# My-Stomp_1_1.net
KiCad netlist of a schematic drawn in EAGLE
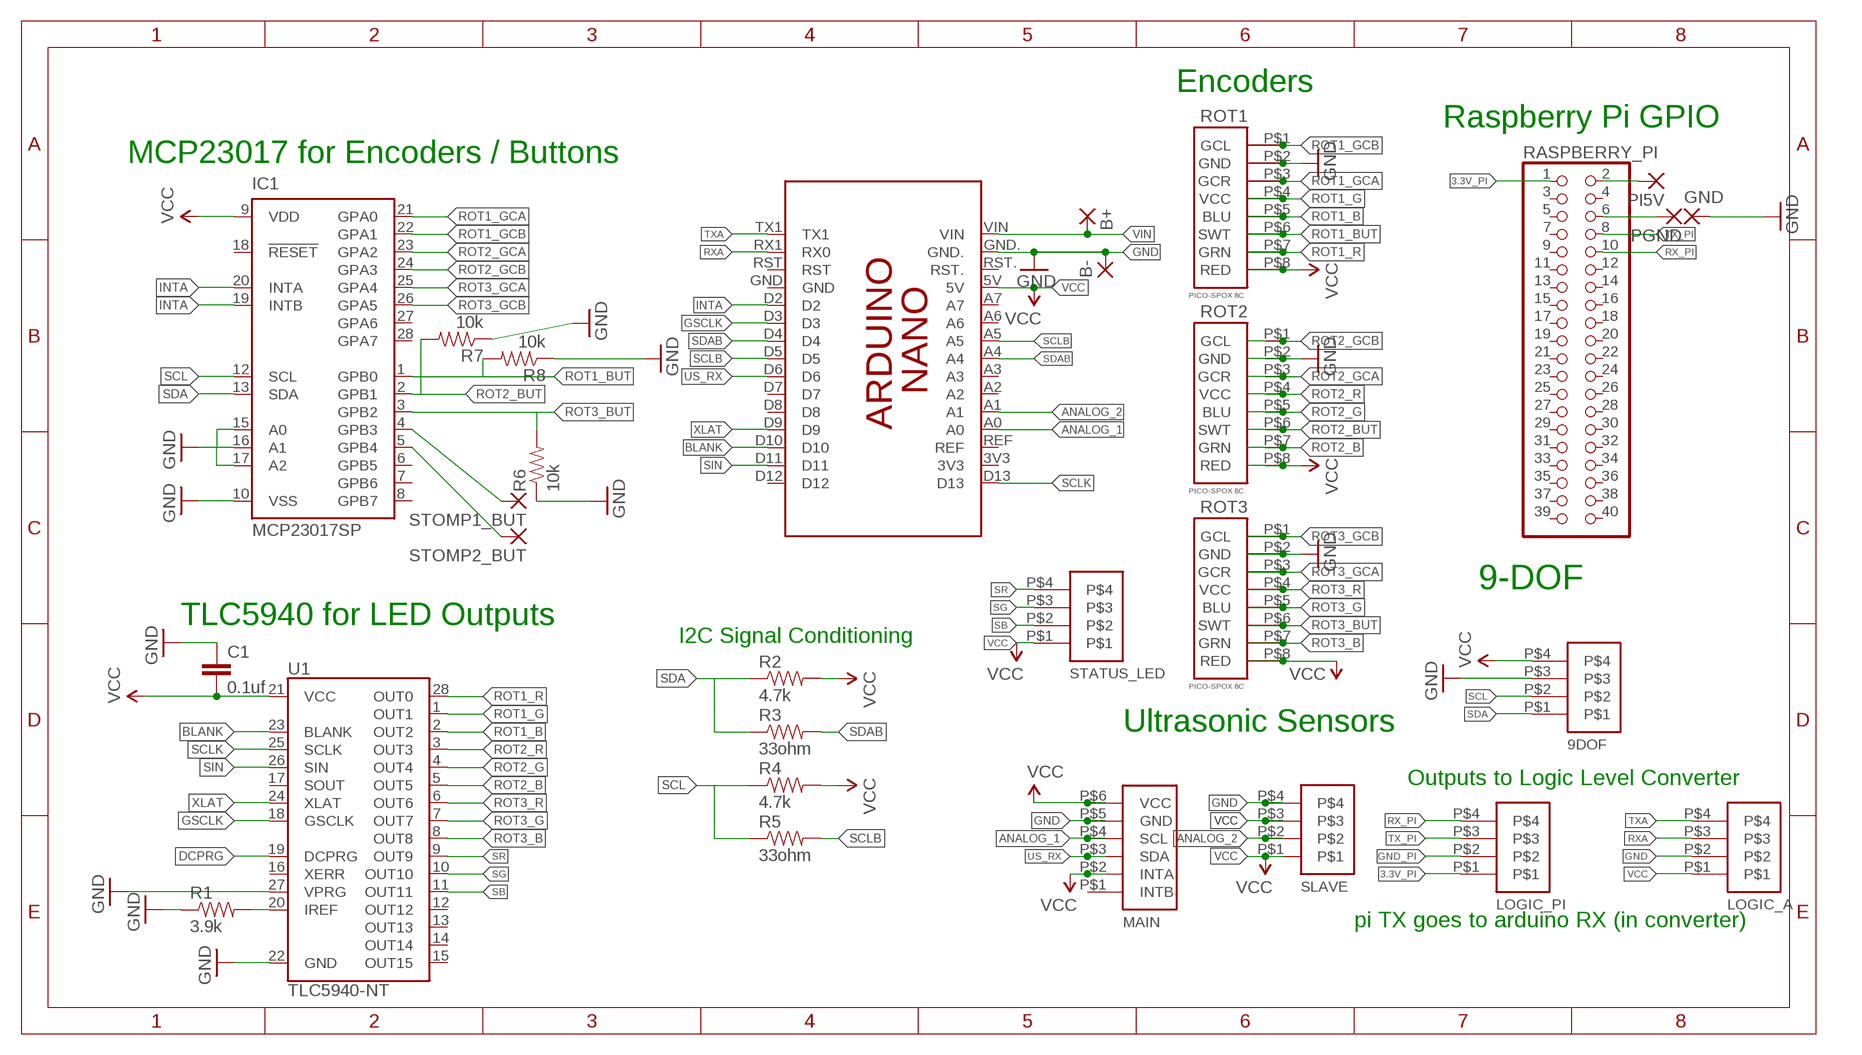
[diagram p0: schematic, sheet 1]

(export (version "E")
  (design (tool "Eeschema 10.0.6"))
  (components
    (comp (ref "9DOF")
      (value "PICO_SPOX_4C")
      (footprint "eagle-import:PICO_SPOX_4C")
      (libsource (lib "eagle-import") (part "PICO_SPOX_4C"))
    )
    (comp (ref "B+")
      (value "2,15/1,0")
      (footprint "eagle-import:2,15_1,0")
      (libsource (lib "eagle-import") (part "2,15/1,0"))
    )
    (comp (ref "B-")
      (value "2,15/1,0")
      (footprint "eagle-import:2,15_1,0")
      (libsource (lib "eagle-import") (part "2,15/1,0"))
    )
    (comp (ref "C1")
      (value "0.1uf")
      (footprint "eagle-import:CAP-PTH-5MM")
      (libsource (lib "eagle-import") (part "CAPPTH1"))
    )
    (comp (ref "GND")
      (value "2,15/1,0")
      (footprint "eagle-import:2,15_1,0")
      (libsource (lib "eagle-import") (part "2,15/1,0"))
    )
    (comp (ref "IC1")
      (value "MCP23017SP")
      (footprint "eagle-import:DIL28-3")
      (libsource (lib "eagle-import") (part "MCP23017SP"))
    )
    (comp (ref "LOGIC_A")
      (value "PICO_SPOX_4C")
      (footprint "eagle-import:PICO_SPOX_4C")
      (libsource (lib "eagle-import") (part "PICO_SPOX_4C"))
    )
    (comp (ref "LOGIC_PI")
      (value "PICO_SPOX_4C")
      (footprint "eagle-import:PICO_SPOX_4C")
      (libsource (lib "eagle-import") (part "PICO_SPOX_4C"))
    )
    (comp (ref "MAIN")
      (value "PICO_SPOX_6C")
      (footprint "eagle-import:PICO_SPOX_6C")
      (libsource (lib "eagle-import") (part "PICO_SPOX_6C"))
    )
    (comp (ref "PCB2")
      (value "ARDUINO_NANO")
      (footprint "eagle-import:ARDUINO_NANO")
      (libsource (lib "eagle-import") (part "ARDUINO_NANO"))
    )
    (comp (ref "PGND")
      (value "2,15/1,0")
      (footprint "eagle-import:2,15_1,0")
      (libsource (lib "eagle-import") (part "2,15/1,0"))
    )
    (comp (ref "PI5V")
      (value "2,15/1,0")
      (footprint "eagle-import:2,15_1,0")
      (libsource (lib "eagle-import") (part "2,15/1,0"))
    )
    (comp (ref "R1")
      (value "3.9k")
      (footprint "eagle-import:AXIAL-0.3")
      (libsource (lib "eagle-import") (part "RESISTORPTH1"))
    )
    (comp (ref "R2")
      (value "4.7k")
      (footprint "eagle-import:AXIAL-0.3")
      (libsource (lib "eagle-import") (part "RESISTORPTH1"))
    )
    (comp (ref "R3")
      (value "33ohm")
      (footprint "eagle-import:AXIAL-0.3")
      (libsource (lib "eagle-import") (part "RESISTORPTH1"))
    )
    (comp (ref "R4")
      (value "4.7k")
      (footprint "eagle-import:AXIAL-0.3")
      (libsource (lib "eagle-import") (part "RESISTORPTH1"))
    )
    (comp (ref "R5")
      (value "33ohm")
      (footprint "eagle-import:AXIAL-0.3")
      (libsource (lib "eagle-import") (part "RESISTORPTH1"))
    )
    (comp (ref "R6")
      (value "10k")
      (footprint "eagle-import:AXIAL-0.3")
      (libsource (lib "eagle-import") (part "RESISTORPTH1"))
    )
    (comp (ref "R7")
      (value "10k")
      (footprint "eagle-import:AXIAL-0.3")
      (libsource (lib "eagle-import") (part "RESISTORPTH1"))
    )
    (comp (ref "R8")
      (value "10k")
      (footprint "eagle-import:AXIAL-0.3")
      (libsource (lib "eagle-import") (part "RESISTORPTH1"))
    )
    (comp (ref "RASPBERRY_PI")
      (value "PINHD-2X20")
      (footprint "eagle-import:2X20")
      (libsource (lib "eagle-import") (part "PINHD-2X20"))
    )
    (comp (ref "ROT1")
      (value "PICO_SPOX_8C")
      (footprint "eagle-import:PICO_SPOC_8C")
      (libsource (lib "eagle-import") (part "PICO_SPOX_8C"))
    )
    (comp (ref "ROT2")
      (value "PICO_SPOX_8C")
      (footprint "eagle-import:PICO_SPOC_8C")
      (libsource (lib "eagle-import") (part "PICO_SPOX_8C"))
    )
    (comp (ref "ROT3")
      (value "PICO_SPOX_8C")
      (footprint "eagle-import:PICO_SPOC_8C")
      (libsource (lib "eagle-import") (part "PICO_SPOX_8C"))
    )
    (comp (ref "SLAVE")
      (value "PICO_SPOX_4C")
      (footprint "eagle-import:PICO_SPOX_4C")
      (libsource (lib "eagle-import") (part "PICO_SPOX_4C"))
    )
    (comp (ref "STATUS_LED")
      (value "PICO_SPOX_4C")
      (footprint "eagle-import:PICO_SPOX_4C")
      (libsource (lib "eagle-import") (part "PICO_SPOX_4C"))
    )
    (comp (ref "STOMP1_BUT")
      (value "2,15/1,0")
      (footprint "eagle-import:2,15_1,0")
      (libsource (lib "eagle-import") (part "2,15/1,0"))
    )
    (comp (ref "STOMP2_BUT")
      (value "2,15/1,0")
      (footprint "eagle-import:2,15_1,0")
      (libsource (lib "eagle-import") (part "2,15/1,0"))
    )
    (comp (ref "U1")
      (value "TLC5940-NT")
      (footprint "eagle-import:DIL28-3")
      (libsource (lib "eagle-import") (part "TLC5940-NT"))
    )
  )
  (nets
    (net (code "1") (name "3.3V_PI") (class "Default")
      (node (ref "LOGIC_PI") (pin "P$1") (pinfunction "P$1_P$1") (pintype "bidirectional"))
      (node (ref "RASPBERRY_PI") (pin "1") (pinfunction "1_1") (pintype "passive"))
    )
    (net (code "2") (name "ANALOG_1") (class "Default")
      (node (ref "MAIN") (pin "P$4") (pinfunction "SCL_P$4") (pintype "bidirectional"))
      (node (ref "PCB2") (pin "A0") (pinfunction "A0_A0") (pintype "bidirectional"))
    )
    (net (code "3") (name "ANALOG_2") (class "Default")
      (node (ref "PCB2") (pin "A1") (pinfunction "A1_A1") (pintype "bidirectional"))
      (node (ref "SLAVE") (pin "P$2") (pinfunction "P$2_P$2") (pintype "bidirectional"))
    )
    (net (code "4") (name "BLANK") (class "Default")
      (node (ref "PCB2") (pin "D10") (pinfunction "D10_D10") (pintype "bidirectional"))
      (node (ref "U1") (pin "23") (pinfunction "BLANK_23") (pintype "bidirectional"))
    )
    (net (code "5") (name "DCPRG") (class "Default")
      (node (ref "U1") (pin "19") (pinfunction "DCPRG_19") (pintype "bidirectional"))
    )
    (net (code "6") (name "GND") (class "Default")
      (node (ref "9DOF") (pin "P$3") (pinfunction "P$3_P$3") (pintype "bidirectional"))
      (node (ref "B-") (pin "1") (pinfunction "P_1") (pintype "passive"))
      (node (ref "C1") (pin "1") (pinfunction "1_1") (pintype "passive"))
      (node (ref "GND") (pin "1") (pinfunction "P_1") (pintype "passive"))
      (node (ref "IC1") (pin "10") (pinfunction "VSS_10") (pintype "power_in"))
      (node (ref "IC1") (pin "15") (pinfunction "A0_15") (pintype "input"))
      (node (ref "IC1") (pin "16") (pinfunction "A1_16") (pintype "input"))
      (node (ref "IC1") (pin "17") (pinfunction "A2_17") (pintype "input"))
      (node (ref "LOGIC_A") (pin "P$2") (pinfunction "P$2_P$2") (pintype "bidirectional"))
      (node (ref "MAIN") (pin "P$5") (pinfunction "GND_P$5") (pintype "bidirectional"))
      (node (ref "PCB2") (pin "GND.") (pinfunction "GND._GND.") (pintype "bidirectional"))
      (node (ref "R1") (pin "P$1") (pinfunction "1_P$1") (pintype "passive"))
      (node (ref "R6") (pin "P$1") (pinfunction "1_P$1") (pintype "passive"))
      (node (ref "R7") (pin "P$1") (pinfunction "1_P$1") (pintype "passive"))
      (node (ref "R8") (pin "P$1") (pinfunction "1_P$1") (pintype "passive"))
      (node (ref "ROT1") (pin "P$2") (pinfunction "GND_P$2") (pintype "bidirectional"))
      (node (ref "ROT2") (pin "P$2") (pinfunction "GND_P$2") (pintype "bidirectional"))
      (node (ref "ROT3") (pin "P$2") (pinfunction "GND_P$2") (pintype "bidirectional"))
      (node (ref "SLAVE") (pin "P$4") (pinfunction "P$4_P$4") (pintype "bidirectional"))
      (node (ref "U1") (pin "22") (pinfunction "GND_22") (pintype "bidirectional"))
      (node (ref "U1") (pin "27") (pinfunction "VPRG_27") (pintype "bidirectional"))
    )
    (net (code "7") (name "GND_PI") (class "Default")
      (node (ref "LOGIC_PI") (pin "P$2") (pinfunction "P$2_P$2") (pintype "bidirectional"))
      (node (ref "PGND") (pin "1") (pinfunction "P_1") (pintype "passive"))
      (node (ref "RASPBERRY_PI") (pin "6") (pinfunction "6_6") (pintype "passive"))
    )
    (net (code "8") (name "GSCLK") (class "Default")
      (node (ref "PCB2") (pin "D3") (pinfunction "D3_D3") (pintype "bidirectional"))
      (node (ref "U1") (pin "18") (pinfunction "GSCLK_18") (pintype "bidirectional"))
    )
    (net (code "9") (name "INTA") (class "Default")
      (node (ref "IC1") (pin "19") (pinfunction "INTB_19") (pintype "output"))
      (node (ref "IC1") (pin "20") (pinfunction "INTA_20") (pintype "output"))
      (node (ref "PCB2") (pin "D2") (pinfunction "D2_D2") (pintype "bidirectional"))
    )
    (net (code "10") (name "Net-(IC1-GPB3)") (class "Default")
      (node (ref "IC1") (pin "4") (pinfunction "GPB3_4") (pintype "bidirectional"))
      (node (ref "STOMP1_BUT") (pin "1") (pinfunction "P_1") (pintype "passive"))
    )
    (net (code "11") (name "Net-(IC1-GPB4)") (class "Default")
      (node (ref "IC1") (pin "5") (pinfunction "GPB4_5") (pintype "bidirectional"))
      (node (ref "STOMP2_BUT") (pin "1") (pinfunction "P_1") (pintype "passive"))
    )
    (net (code "12") (name "Net-(PI5V-P)") (class "Default")
      (node (ref "PI5V") (pin "1") (pinfunction "P_1") (pintype "passive"))
      (node (ref "RASPBERRY_PI") (pin "2") (pinfunction "2_2") (pintype "passive"))
    )
    (net (code "13") (name "Net-(R1-2)") (class "Default")
      (node (ref "R1") (pin "P$2") (pinfunction "2_P$2") (pintype "passive"))
      (node (ref "U1") (pin "20") (pinfunction "IREF_20") (pintype "bidirectional"))
    )
    (net (code "14") (name "ROT1_B") (class "Default")
      (node (ref "ROT1") (pin "P$5") (pinfunction "BLU_P$5") (pintype "bidirectional"))
      (node (ref "U1") (pin "2") (pinfunction "OUT2_2") (pintype "bidirectional"))
    )
    (net (code "15") (name "ROT1_BUT") (class "Default")
      (node (ref "IC1") (pin "1") (pinfunction "GPB0_1") (pintype "bidirectional"))
      (node (ref "R8") (pin "P$2") (pinfunction "2_P$2") (pintype "passive"))
      (node (ref "ROT1") (pin "P$6") (pinfunction "SWT_P$6") (pintype "bidirectional"))
    )
    (net (code "16") (name "ROT1_G") (class "Default")
      (node (ref "ROT1") (pin "P$4") (pinfunction "VCC_P$4") (pintype "bidirectional"))
      (node (ref "U1") (pin "1") (pinfunction "OUT1_1") (pintype "bidirectional"))
    )
    (net (code "17") (name "ROT1_GCA") (class "Default")
      (node (ref "IC1") (pin "21") (pinfunction "GPA0_21") (pintype "bidirectional"))
      (node (ref "ROT1") (pin "P$3") (pinfunction "GCR_P$3") (pintype "bidirectional"))
    )
    (net (code "18") (name "ROT1_GCB") (class "Default")
      (node (ref "IC1") (pin "22") (pinfunction "GPA1_22") (pintype "bidirectional"))
      (node (ref "ROT1") (pin "P$1") (pinfunction "GCL_P$1") (pintype "bidirectional"))
    )
    (net (code "19") (name "ROT1_R") (class "Default")
      (node (ref "ROT1") (pin "P$7") (pinfunction "GRN_P$7") (pintype "bidirectional"))
      (node (ref "U1") (pin "28") (pinfunction "OUT0_28") (pintype "bidirectional"))
    )
    (net (code "20") (name "ROT2_B") (class "Default")
      (node (ref "ROT2") (pin "P$7") (pinfunction "GRN_P$7") (pintype "bidirectional"))
      (node (ref "U1") (pin "5") (pinfunction "OUT5_5") (pintype "bidirectional"))
    )
    (net (code "21") (name "ROT2_BUT") (class "Default")
      (node (ref "IC1") (pin "2") (pinfunction "GPB1_2") (pintype "bidirectional"))
      (node (ref "R7") (pin "P$2") (pinfunction "2_P$2") (pintype "passive"))
      (node (ref "ROT2") (pin "P$6") (pinfunction "SWT_P$6") (pintype "bidirectional"))
    )
    (net (code "22") (name "ROT2_G") (class "Default")
      (node (ref "ROT2") (pin "P$5") (pinfunction "BLU_P$5") (pintype "bidirectional"))
      (node (ref "U1") (pin "4") (pinfunction "OUT4_4") (pintype "bidirectional"))
    )
    (net (code "23") (name "ROT2_GCA") (class "Default")
      (node (ref "IC1") (pin "23") (pinfunction "GPA2_23") (pintype "bidirectional"))
      (node (ref "ROT2") (pin "P$3") (pinfunction "GCR_P$3") (pintype "bidirectional"))
    )
    (net (code "24") (name "ROT2_GCB") (class "Default")
      (node (ref "IC1") (pin "24") (pinfunction "GPA3_24") (pintype "bidirectional"))
      (node (ref "ROT2") (pin "P$1") (pinfunction "GCL_P$1") (pintype "bidirectional"))
    )
    (net (code "25") (name "ROT2_R") (class "Default")
      (node (ref "ROT2") (pin "P$4") (pinfunction "VCC_P$4") (pintype "bidirectional"))
      (node (ref "U1") (pin "3") (pinfunction "OUT3_3") (pintype "bidirectional"))
    )
    (net (code "26") (name "ROT3_B") (class "Default")
      (node (ref "ROT3") (pin "P$7") (pinfunction "GRN_P$7") (pintype "bidirectional"))
      (node (ref "U1") (pin "8") (pinfunction "OUT8_8") (pintype "bidirectional"))
    )
    (net (code "27") (name "ROT3_BUT") (class "Default")
      (node (ref "IC1") (pin "3") (pinfunction "GPB2_3") (pintype "bidirectional"))
      (node (ref "R6") (pin "P$2") (pinfunction "2_P$2") (pintype "passive"))
      (node (ref "ROT3") (pin "P$6") (pinfunction "SWT_P$6") (pintype "bidirectional"))
    )
    (net (code "28") (name "ROT3_G") (class "Default")
      (node (ref "ROT3") (pin "P$5") (pinfunction "BLU_P$5") (pintype "bidirectional"))
      (node (ref "U1") (pin "7") (pinfunction "OUT7_7") (pintype "bidirectional"))
    )
    (net (code "29") (name "ROT3_GCA") (class "Default")
      (node (ref "IC1") (pin "25") (pinfunction "GPA4_25") (pintype "bidirectional"))
      (node (ref "ROT3") (pin "P$3") (pinfunction "GCR_P$3") (pintype "bidirectional"))
    )
    (net (code "30") (name "ROT3_GCB") (class "Default")
      (node (ref "IC1") (pin "26") (pinfunction "GPA5_26") (pintype "bidirectional"))
      (node (ref "ROT3") (pin "P$1") (pinfunction "GCL_P$1") (pintype "bidirectional"))
    )
    (net (code "31") (name "ROT3_R") (class "Default")
      (node (ref "ROT3") (pin "P$4") (pinfunction "VCC_P$4") (pintype "bidirectional"))
      (node (ref "U1") (pin "6") (pinfunction "OUT6_6") (pintype "bidirectional"))
    )
    (net (code "32") (name "RXA") (class "Default")
      (node (ref "LOGIC_A") (pin "P$3") (pinfunction "P$3_P$3") (pintype "bidirectional"))
      (node (ref "PCB2") (pin "RX1") (pinfunction "RX0_RX1") (pintype "bidirectional"))
    )
    (net (code "33") (name "RX_PI") (class "Default")
      (node (ref "LOGIC_PI") (pin "P$4") (pinfunction "P$4_P$4") (pintype "bidirectional"))
      (node (ref "RASPBERRY_PI") (pin "10") (pinfunction "10_10") (pintype "passive"))
    )
    (net (code "34") (name "SB") (class "Default")
      (node (ref "STATUS_LED") (pin "P$2") (pinfunction "P$2_P$2") (pintype "bidirectional"))
      (node (ref "U1") (pin "11") (pinfunction "OUT11_11") (pintype "bidirectional"))
    )
    (net (code "35") (name "SCL") (class "Default")
      (node (ref "9DOF") (pin "P$2") (pinfunction "P$2_P$2") (pintype "bidirectional"))
      (node (ref "IC1") (pin "12") (pinfunction "SCL_12") (pintype "input"))
      (node (ref "R4") (pin "P$1") (pinfunction "1_P$1") (pintype "passive"))
      (node (ref "R5") (pin "P$1") (pinfunction "1_P$1") (pintype "passive"))
    )
    (net (code "36") (name "SCLB") (class "Default")
      (node (ref "PCB2") (pin "A5") (pinfunction "A5_A5") (pintype "bidirectional"))
      (node (ref "PCB2") (pin "D5") (pinfunction "D5_D5") (pintype "bidirectional"))
      (node (ref "R5") (pin "P$2") (pinfunction "2_P$2") (pintype "passive"))
    )
    (net (code "37") (name "SCLK") (class "Default")
      (node (ref "PCB2") (pin "D13") (pinfunction "D13_D13") (pintype "bidirectional"))
      (node (ref "U1") (pin "25") (pinfunction "SCLK_25") (pintype "bidirectional"))
    )
    (net (code "38") (name "SDA") (class "Default")
      (node (ref "9DOF") (pin "P$1") (pinfunction "P$1_P$1") (pintype "bidirectional"))
      (node (ref "IC1") (pin "13") (pinfunction "SDA_13") (pintype "bidirectional"))
      (node (ref "R2") (pin "P$1") (pinfunction "1_P$1") (pintype "passive"))
      (node (ref "R3") (pin "P$1") (pinfunction "1_P$1") (pintype "passive"))
    )
    (net (code "39") (name "SDAB") (class "Default")
      (node (ref "PCB2") (pin "A4") (pinfunction "A4_A4") (pintype "bidirectional"))
      (node (ref "PCB2") (pin "D4") (pinfunction "D4_D4") (pintype "bidirectional"))
      (node (ref "R3") (pin "P$2") (pinfunction "2_P$2") (pintype "passive"))
    )
    (net (code "40") (name "SG") (class "Default")
      (node (ref "STATUS_LED") (pin "P$3") (pinfunction "P$3_P$3") (pintype "bidirectional"))
      (node (ref "U1") (pin "10") (pinfunction "OUT10_10") (pintype "bidirectional"))
    )
    (net (code "41") (name "SIN") (class "Default")
      (node (ref "PCB2") (pin "D11") (pinfunction "D11_D11") (pintype "bidirectional"))
      (node (ref "U1") (pin "26") (pinfunction "SIN_26") (pintype "bidirectional"))
    )
    (net (code "42") (name "SR") (class "Default")
      (node (ref "STATUS_LED") (pin "P$4") (pinfunction "P$4_P$4") (pintype "bidirectional"))
      (node (ref "U1") (pin "9") (pinfunction "OUT9_9") (pintype "bidirectional"))
    )
    (net (code "43") (name "TXA") (class "Default")
      (node (ref "LOGIC_A") (pin "P$4") (pinfunction "P$4_P$4") (pintype "bidirectional"))
      (node (ref "PCB2") (pin "TX1") (pinfunction "TX1_TX1") (pintype "bidirectional"))
    )
    (net (code "44") (name "TX_PI") (class "Default")
      (node (ref "LOGIC_PI") (pin "P$3") (pinfunction "P$3_P$3") (pintype "bidirectional"))
      (node (ref "RASPBERRY_PI") (pin "8") (pinfunction "8_8") (pintype "passive"))
    )
    (net (code "45") (name "US_RX") (class "Default")
      (node (ref "MAIN") (pin "P$3") (pinfunction "SDA_P$3") (pintype "bidirectional"))
      (node (ref "PCB2") (pin "D6") (pinfunction "D6_D6") (pintype "bidirectional"))
    )
    (net (code "46") (name "VCC") (class "Default")
      (node (ref "9DOF") (pin "P$4") (pinfunction "P$4_P$4") (pintype "bidirectional"))
      (node (ref "C1") (pin "2") (pinfunction "2_2") (pintype "passive"))
      (node (ref "IC1") (pin "9") (pinfunction "VDD_9") (pintype "power_in"))
      (node (ref "LOGIC_A") (pin "P$1") (pinfunction "P$1_P$1") (pintype "bidirectional"))
      (node (ref "MAIN") (pin "P$2") (pinfunction "INTA_P$2") (pintype "bidirectional"))
      (node (ref "MAIN") (pin "P$6") (pinfunction "VCC_P$6") (pintype "bidirectional"))
      (node (ref "PCB2") (pin "5V") (pinfunction "5V_5V") (pintype "bidirectional"))
      (node (ref "R2") (pin "P$2") (pinfunction "2_P$2") (pintype "passive"))
      (node (ref "R4") (pin "P$2") (pinfunction "2_P$2") (pintype "passive"))
      (node (ref "ROT1") (pin "P$8") (pinfunction "RED_P$8") (pintype "bidirectional"))
      (node (ref "ROT2") (pin "P$8") (pinfunction "RED_P$8") (pintype "bidirectional"))
      (node (ref "ROT3") (pin "P$8") (pinfunction "RED_P$8") (pintype "bidirectional"))
      (node (ref "SLAVE") (pin "P$1") (pinfunction "P$1_P$1") (pintype "bidirectional"))
      (node (ref "SLAVE") (pin "P$3") (pinfunction "P$3_P$3") (pintype "bidirectional"))
      (node (ref "STATUS_LED") (pin "P$1") (pinfunction "P$1_P$1") (pintype "bidirectional"))
      (node (ref "U1") (pin "21") (pinfunction "VCC_21") (pintype "bidirectional"))
    )
    (net (code "47") (name "VIN") (class "Default")
      (node (ref "B+") (pin "1") (pinfunction "P_1") (pintype "passive"))
      (node (ref "PCB2") (pin "VIN") (pinfunction "VIN_VIN") (pintype "bidirectional"))
    )
    (net (code "48") (name "XLAT") (class "Default")
      (node (ref "PCB2") (pin "D9") (pinfunction "D9_D9") (pintype "bidirectional"))
      (node (ref "U1") (pin "24") (pinfunction "XLAT_24") (pintype "bidirectional"))
    )
    (net (code "49") (name "unconnected-(IC1-GPA6-Pad27)") (class "Default")
      (node (ref "IC1") (pin "27") (pinfunction "GPA6_27") (pintype "bidirectional"))
    )
    (net (code "50") (name "unconnected-(IC1-GPA7-Pad28)") (class "Default")
      (node (ref "IC1") (pin "28") (pinfunction "GPA7_28") (pintype "bidirectional"))
    )
    (net (code "51") (name "unconnected-(IC1-GPB5-Pad6)") (class "Default")
      (node (ref "IC1") (pin "6") (pinfunction "GPB5_6") (pintype "bidirectional"))
    )
    (net (code "52") (name "unconnected-(IC1-GPB6-Pad7)") (class "Default")
      (node (ref "IC1") (pin "7") (pinfunction "GPB6_7") (pintype "bidirectional"))
    )
    (net (code "53") (name "unconnected-(IC1-GPB7-Pad8)") (class "Default")
      (node (ref "IC1") (pin "8") (pinfunction "GPB7_8") (pintype "bidirectional"))
    )
    (net (code "54") (name "unconnected-(IC1-~{RESET}-Pad18)") (class "Default")
      (node (ref "IC1") (pin "18") (pinfunction "~{RESET}_18") (pintype "input"))
    )
    (net (code "55") (name "unconnected-(MAIN-INTB-PadP$1)") (class "Default")
      (node (ref "MAIN") (pin "P$1") (pinfunction "INTB_P$1") (pintype "bidirectional"))
    )
    (net (code "56") (name "unconnected-(PCB2-Pad3V3)") (class "Default")
      (node (ref "PCB2") (pin "3V3") (pinfunction "3V3_3V3") (pintype "bidirectional"))
    )
    (net (code "57") (name "unconnected-(PCB2-PadA2)") (class "Default")
      (node (ref "PCB2") (pin "A2") (pinfunction "A2_A2") (pintype "bidirectional"))
    )
    (net (code "58") (name "unconnected-(PCB2-PadA3)") (class "Default")
      (node (ref "PCB2") (pin "A3") (pinfunction "A3_A3") (pintype "bidirectional"))
    )
    (net (code "59") (name "unconnected-(PCB2-PadA6)") (class "Default")
      (node (ref "PCB2") (pin "A6") (pinfunction "A6_A6") (pintype "bidirectional"))
    )
    (net (code "60") (name "unconnected-(PCB2-PadA7)") (class "Default")
      (node (ref "PCB2") (pin "A7") (pinfunction "A7_A7") (pintype "bidirectional"))
    )
    (net (code "61") (name "unconnected-(PCB2-PadD7)") (class "Default")
      (node (ref "PCB2") (pin "D7") (pinfunction "D7_D7") (pintype "bidirectional"))
    )
    (net (code "62") (name "unconnected-(PCB2-PadD8)") (class "Default")
      (node (ref "PCB2") (pin "D8") (pinfunction "D8_D8") (pintype "bidirectional"))
    )
    (net (code "63") (name "unconnected-(PCB2-PadD12)") (class "Default")
      (node (ref "PCB2") (pin "D12") (pinfunction "D12_D12") (pintype "bidirectional"))
    )
    (net (code "64") (name "unconnected-(PCB2-PadGND)") (class "Default")
      (node (ref "PCB2") (pin "GND") (pinfunction "GND_GND") (pintype "bidirectional"))
    )
    (net (code "65") (name "unconnected-(PCB2-PadREF)") (class "Default")
      (node (ref "PCB2") (pin "REF") (pinfunction "REF_REF") (pintype "bidirectional"))
    )
    (net (code "66") (name "unconnected-(PCB2-PadRST)") (class "Default")
      (node (ref "PCB2") (pin "RST") (pinfunction "RST_RST") (pintype "bidirectional"))
    )
    (net (code "67") (name "unconnected-(PCB2-PadRST.)") (class "Default")
      (node (ref "PCB2") (pin "RST.") (pinfunction "RST._RST.") (pintype "bidirectional"))
    )
    (net (code "68") (name "unconnected-(RASPBERRY_PI-Pad3)") (class "Default")
      (node (ref "RASPBERRY_PI") (pin "3") (pinfunction "3_3") (pintype "passive"))
    )
    (net (code "69") (name "unconnected-(RASPBERRY_PI-Pad4)") (class "Default")
      (node (ref "RASPBERRY_PI") (pin "4") (pinfunction "4_4") (pintype "passive"))
    )
    (net (code "70") (name "unconnected-(RASPBERRY_PI-Pad5)") (class "Default")
      (node (ref "RASPBERRY_PI") (pin "5") (pinfunction "5_5") (pintype "passive"))
    )
    (net (code "71") (name "unconnected-(RASPBERRY_PI-Pad7)") (class "Default")
      (node (ref "RASPBERRY_PI") (pin "7") (pinfunction "7_7") (pintype "passive"))
    )
    (net (code "72") (name "unconnected-(RASPBERRY_PI-Pad9)") (class "Default")
      (node (ref "RASPBERRY_PI") (pin "9") (pinfunction "9_9") (pintype "passive"))
    )
    (net (code "73") (name "unconnected-(RASPBERRY_PI-Pad11)") (class "Default")
      (node (ref "RASPBERRY_PI") (pin "11") (pinfunction "11_11") (pintype "passive"))
    )
    (net (code "74") (name "unconnected-(RASPBERRY_PI-Pad12)") (class "Default")
      (node (ref "RASPBERRY_PI") (pin "12") (pinfunction "12_12") (pintype "passive"))
    )
    (net (code "75") (name "unconnected-(RASPBERRY_PI-Pad13)") (class "Default")
      (node (ref "RASPBERRY_PI") (pin "13") (pinfunction "13_13") (pintype "passive"))
    )
    (net (code "76") (name "unconnected-(RASPBERRY_PI-Pad14)") (class "Default")
      (node (ref "RASPBERRY_PI") (pin "14") (pinfunction "14_14") (pintype "passive"))
    )
    (net (code "77") (name "unconnected-(RASPBERRY_PI-Pad15)") (class "Default")
      (node (ref "RASPBERRY_PI") (pin "15") (pinfunction "15_15") (pintype "passive"))
    )
    (net (code "78") (name "unconnected-(RASPBERRY_PI-Pad16)") (class "Default")
      (node (ref "RASPBERRY_PI") (pin "16") (pinfunction "16_16") (pintype "passive"))
    )
    (net (code "79") (name "unconnected-(RASPBERRY_PI-Pad17)") (class "Default")
      (node (ref "RASPBERRY_PI") (pin "17") (pinfunction "17_17") (pintype "passive"))
    )
    (net (code "80") (name "unconnected-(RASPBERRY_PI-Pad18)") (class "Default")
      (node (ref "RASPBERRY_PI") (pin "18") (pinfunction "18_18") (pintype "passive"))
    )
    (net (code "81") (name "unconnected-(RASPBERRY_PI-Pad19)") (class "Default")
      (node (ref "RASPBERRY_PI") (pin "19") (pinfunction "19_19") (pintype "passive"))
    )
    (net (code "82") (name "unconnected-(RASPBERRY_PI-Pad20)") (class "Default")
      (node (ref "RASPBERRY_PI") (pin "20") (pinfunction "20_20") (pintype "passive"))
    )
    (net (code "83") (name "unconnected-(RASPBERRY_PI-Pad21)") (class "Default")
      (node (ref "RASPBERRY_PI") (pin "21") (pinfunction "21_21") (pintype "passive"))
    )
    (net (code "84") (name "unconnected-(RASPBERRY_PI-Pad22)") (class "Default")
      (node (ref "RASPBERRY_PI") (pin "22") (pinfunction "22_22") (pintype "passive"))
    )
    (net (code "85") (name "unconnected-(RASPBERRY_PI-Pad23)") (class "Default")
      (node (ref "RASPBERRY_PI") (pin "23") (pinfunction "23_23") (pintype "passive"))
    )
    (net (code "86") (name "unconnected-(RASPBERRY_PI-Pad24)") (class "Default")
      (node (ref "RASPBERRY_PI") (pin "24") (pinfunction "24_24") (pintype "passive"))
    )
    (net (code "87") (name "unconnected-(RASPBERRY_PI-Pad25)") (class "Default")
      (node (ref "RASPBERRY_PI") (pin "25") (pinfunction "25_25") (pintype "passive"))
    )
    (net (code "88") (name "unconnected-(RASPBERRY_PI-Pad26)") (class "Default")
      (node (ref "RASPBERRY_PI") (pin "26") (pinfunction "26_26") (pintype "passive"))
    )
    (net (code "89") (name "unconnected-(RASPBERRY_PI-Pad27)") (class "Default")
      (node (ref "RASPBERRY_PI") (pin "27") (pinfunction "27_27") (pintype "passive"))
    )
    (net (code "90") (name "unconnected-(RASPBERRY_PI-Pad28)") (class "Default")
      (node (ref "RASPBERRY_PI") (pin "28") (pinfunction "28_28") (pintype "passive"))
    )
    (net (code "91") (name "unconnected-(RASPBERRY_PI-Pad29)") (class "Default")
      (node (ref "RASPBERRY_PI") (pin "29") (pinfunction "29_29") (pintype "passive"))
    )
    (net (code "92") (name "unconnected-(RASPBERRY_PI-Pad30)") (class "Default")
      (node (ref "RASPBERRY_PI") (pin "30") (pinfunction "30_30") (pintype "passive"))
    )
    (net (code "93") (name "unconnected-(RASPBERRY_PI-Pad31)") (class "Default")
      (node (ref "RASPBERRY_PI") (pin "31") (pinfunction "31_31") (pintype "passive"))
    )
    (net (code "94") (name "unconnected-(RASPBERRY_PI-Pad32)") (class "Default")
      (node (ref "RASPBERRY_PI") (pin "32") (pinfunction "32_32") (pintype "passive"))
    )
    (net (code "95") (name "unconnected-(RASPBERRY_PI-Pad33)") (class "Default")
      (node (ref "RASPBERRY_PI") (pin "33") (pinfunction "33_33") (pintype "passive"))
    )
    (net (code "96") (name "unconnected-(RASPBERRY_PI-Pad34)") (class "Default")
      (node (ref "RASPBERRY_PI") (pin "34") (pinfunction "34_34") (pintype "passive"))
    )
    (net (code "97") (name "unconnected-(RASPBERRY_PI-Pad35)") (class "Default")
      (node (ref "RASPBERRY_PI") (pin "35") (pinfunction "35_35") (pintype "passive"))
    )
    (net (code "98") (name "unconnected-(RASPBERRY_PI-Pad36)") (class "Default")
      (node (ref "RASPBERRY_PI") (pin "36") (pinfunction "36_36") (pintype "passive"))
    )
    (net (code "99") (name "unconnected-(RASPBERRY_PI-Pad37)") (class "Default")
      (node (ref "RASPBERRY_PI") (pin "37") (pinfunction "37_37") (pintype "passive"))
    )
    (net (code "100") (name "unconnected-(RASPBERRY_PI-Pad38)") (class "Default")
      (node (ref "RASPBERRY_PI") (pin "38") (pinfunction "38_38") (pintype "passive"))
    )
    (net (code "101") (name "unconnected-(RASPBERRY_PI-Pad39)") (class "Default")
      (node (ref "RASPBERRY_PI") (pin "39") (pinfunction "39_39") (pintype "passive"))
    )
    (net (code "102") (name "unconnected-(RASPBERRY_PI-Pad40)") (class "Default")
      (node (ref "RASPBERRY_PI") (pin "40") (pinfunction "40_40") (pintype "passive"))
    )
    (net (code "103") (name "unconnected-(U1-OUT12-Pad12)") (class "Default")
      (node (ref "U1") (pin "12") (pinfunction "OUT12_12") (pintype "bidirectional"))
    )
    (net (code "104") (name "unconnected-(U1-OUT13-Pad13)") (class "Default")
      (node (ref "U1") (pin "13") (pinfunction "OUT13_13") (pintype "bidirectional"))
    )
    (net (code "105") (name "unconnected-(U1-OUT14-Pad14)") (class "Default")
      (node (ref "U1") (pin "14") (pinfunction "OUT14_14") (pintype "bidirectional"))
    )
    (net (code "106") (name "unconnected-(U1-OUT15-Pad15)") (class "Default")
      (node (ref "U1") (pin "15") (pinfunction "OUT15_15") (pintype "bidirectional"))
    )
    (net (code "107") (name "unconnected-(U1-SOUT-Pad17)") (class "Default")
      (node (ref "U1") (pin "17") (pinfunction "SOUT_17") (pintype "bidirectional"))
    )
    (net (code "108") (name "unconnected-(U1-XERR-Pad16)") (class "Default")
      (node (ref "U1") (pin "16") (pinfunction "XERR_16") (pintype "bidirectional"))
    )
  )
)
